# crowd_chase_el.net
KiCad netlist of a schematic drawn in EAGLE
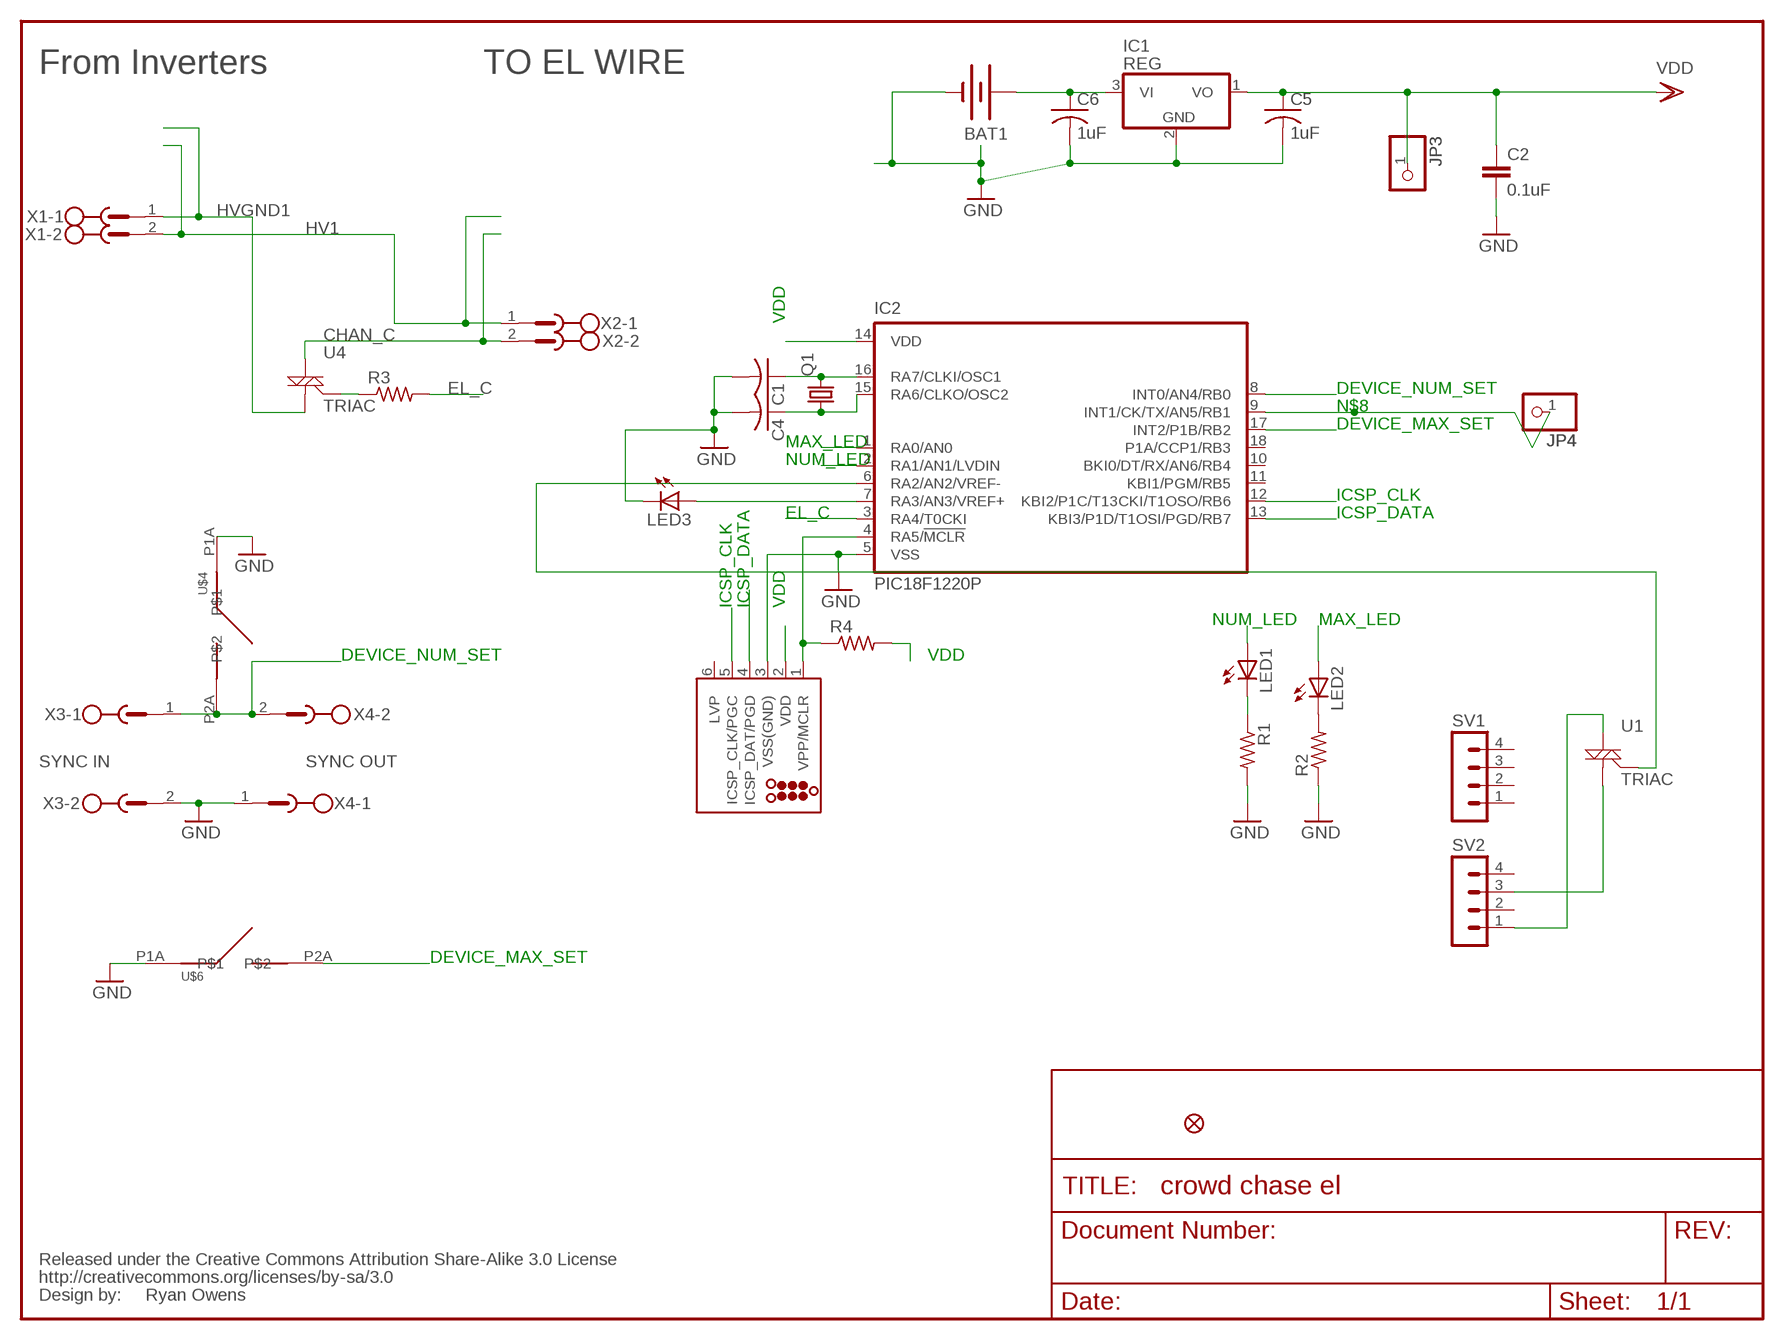
[diagram p0: schematic, sheet 1]

(export (version "E")
  (design (tool "Eeschema 10.0.6"))
  (components
    (comp (ref "BAT1")
      (value "BATTERY20SMD-L")
      (footprint "eagle-import:BATTCON_20MM")
      (libsource (lib "eagle-import") (part "BATTERY20SMD-L"))
    )
    (comp (ref "C1")
      (value "C-US025-025X050")
      (footprint "eagle-import:C025-025X050")
      (libsource (lib "eagle-import") (part "C-US025-025X050"))
    )
    (comp (ref "C2")
      (value "0.1uF")
      (footprint "eagle-import:CAP-PTH-SMALL2")
      (libsource (lib "eagle-import") (part "CAPPTH2"))
    )
    (comp (ref "C4")
      (value "C-US025-025X050")
      (footprint "eagle-import:C025-025X050")
      (libsource (lib "eagle-import") (part "C-US025-025X050"))
    )
    (comp (ref "C5")
      (value "1uF")
      (footprint "eagle-import:C025-025X050")
      (libsource (lib "eagle-import") (part "C-US025-025X050"))
    )
    (comp (ref "C6")
      (value "1uF")
      (footprint "eagle-import:C025-025X050")
      (libsource (lib "eagle-import") (part "C-US025-025X050"))
    )
    (comp (ref "IC1")
      (value "REG")
      (footprint "eagle-import:TO92")
      (libsource (lib "eagle-import") (part "78L05"))
    )
    (comp (ref "IC2")
      (value "PIC18F1220P")
      (footprint "eagle-import:DIL18")
      (fields (field (name "MF") "MICROCHIP") (field (name "MPN") "PIC18F1220-I/P"))
      (libsource (lib "eagle-import") (part "PIC18F120P2"))
    )
    (comp (ref "J2")
      (value "TC2030")
      (footprint "eagle-import:TC2030-MCP-NL-CP")
      (libsource (lib "eagle-import") (part "TC2030"))
    )
    (comp (ref "JP3")
      (value "PINHEADER_1X1")
      (footprint "eagle-import:HEADER_DIP_1X01")
      (libsource (lib "eagle-import") (part "PINHEADER_1X1"))
    )
    (comp (ref "JP4")
      (value "PINHEADER_1X1")
      (footprint "eagle-import:HEADER_DIP_1X01")
      (libsource (lib "eagle-import") (part "PINHEADER_1X1"))
    )
    (comp (ref "LED1")
      (value "LED3MM")
      (footprint "eagle-import:LED3MM")
      (libsource (lib "eagle-import") (part "LED3MM"))
    )
    (comp (ref "LED2")
      (value "LED3MM")
      (footprint "eagle-import:LED3MM")
      (libsource (lib "eagle-import") (part "LED3MM"))
    )
    (comp (ref "LED3")
      (value "LED3MM")
      (footprint "eagle-import:LED3MM")
      (libsource (lib "eagle-import") (part "LED3MM"))
    )
    (comp (ref "Q1")
      (value "CRYSTALHC49S")
      (footprint "eagle-import:HC49_S")
      (libsource (lib "eagle-import") (part "CRYSTALHC49S"))
    )
    (comp (ref "R1")
      (value "R-US_0204/5")
      (footprint "eagle-import:0204_5")
      (libsource (lib "eagle-import") (part "resistor_R-US_0204/5"))
    )
    (comp (ref "R2")
      (value "R-US_0204/5")
      (footprint "eagle-import:0204_5")
      (libsource (lib "eagle-import") (part "resistor_R-US_0204/5"))
    )
    (comp (ref "R3")
      (value "R-US_0204/5")
      (footprint "eagle-import:0204_5")
      (libsource (lib "eagle-import") (part "R-US_0204/5"))
    )
    (comp (ref "R4")
      (value "R-US_0204/5")
      (footprint "eagle-import:0204_5")
      (libsource (lib "eagle-import") (part "resistor_R-US_0204/5"))
    )
    (comp (ref "SV1")
      (value "MA04-1")
      (footprint "eagle-import:MA04-1")
      (libsource (lib "eagle-import") (part "MA04-1"))
    )
    (comp (ref "SV2")
      (value "MA04-1")
      (footprint "eagle-import:MA04-1")
      (libsource (lib "eagle-import") (part "MA04-1"))
    )
    (comp (ref "U$2")
      (value "FIDUCIAL1X2")
      (footprint "eagle-import:FIDUCIAL-1X2")
      (libsource (lib "eagle-import") (part "FIDUCIAL1X2"))
    )
    (comp (ref "U$4")
      (value "12MMTACT_MJTP1212")
      (footprint "eagle-import:MJTP1212")
      (libsource (lib "eagle-import") (part "12MMTACT_MJTP1212"))
    )
    (comp (ref "U$5")
      (value "CREATIVE_COMMONS")
      (footprint "eagle-import:CREATIVE_COMMONS")
      (libsource (lib "eagle-import") (part "CREATIVE_COMMONS"))
    )
    (comp (ref "U$6")
      (value "12MMTACT_MJTP1212")
      (footprint "eagle-import:MJTP1212")
      (libsource (lib "eagle-import") (part "12MMTACT_MJTP1212"))
    )
    (comp (ref "U1")
      (value "TRIAC")
      (footprint "eagle-import:TO-92")
      (libsource (lib "eagle-import") (part "TRIACPTH"))
    )
    (comp (ref "U4")
      (value "TRIAC")
      (footprint "eagle-import:TO-92")
      (libsource (lib "eagle-import") (part "TRIACPTH"))
    )
    (comp (ref "X1")
      (value "MSTBV2")
      (footprint "eagle-import:MSTBV2")
      (libsource (lib "eagle-import") (part "MSTBV2"))
    )
    (comp (ref "X2")
      (value "MSTBV2")
      (footprint "eagle-import:MSTBV2")
      (libsource (lib "eagle-import") (part "MSTBV2"))
    )
    (comp (ref "X3")
      (value "MSTBV2")
      (footprint "eagle-import:MSTBV2")
      (libsource (lib "eagle-import") (part "MSTBV2"))
    )
    (comp (ref "X4")
      (value "MSTBV2")
      (footprint "eagle-import:MSTBV2")
      (libsource (lib "eagle-import") (part "MSTBV2"))
    )
  )
  (nets
    (net (code "1") (name "/CHAN_C") (class "Default")
      (node (ref "U4") (pin "3") (pinfunction "M2_3") (pintype "bidirectional"))
      (node (ref "X2") (pin "2") (pinfunction "SK_2") (pintype "passive"))
    )
    (net (code "2") (name "/DEVICE_MAX_SET") (class "Default")
      (node (ref "IC2") (pin "17") (pinfunction "INT2/P1B/RB2_17") (pintype "bidirectional"))
      (node (ref "U$6") (pin "P2A") (pinfunction "P$2_P2A") (pintype "bidirectional"))
    )
    (net (code "3") (name "/DEVICE_NUM_SET") (class "Default")
      (node (ref "IC2") (pin "8") (pinfunction "INT0/AN4/RB0_8") (pintype "bidirectional"))
      (node (ref "U$4") (pin "P2A") (pinfunction "P$2_P2A") (pintype "bidirectional"))
      (node (ref "X3") (pin "1") (pinfunction "SK_1") (pintype "passive"))
      (node (ref "X4") (pin "2") (pinfunction "SK_2") (pintype "passive"))
    )
    (net (code "4") (name "/EL_C") (class "Default")
      (node (ref "IC2") (pin "3") (pinfunction "RA4/T0CKI_3") (pintype "bidirectional"))
      (node (ref "R3") (pin "2") (pinfunction "2_2") (pintype "passive"))
    )
    (net (code "5") (name "/HV1") (class "Default")
      (node (ref "X1") (pin "2") (pinfunction "SK_2") (pintype "passive"))
      (node (ref "X2") (pin "1") (pinfunction "SK_1") (pintype "passive"))
    )
    (net (code "6") (name "/HVGND1") (class "Default")
      (node (ref "U4") (pin "1") (pinfunction "M1_1") (pintype "bidirectional"))
      (node (ref "X1") (pin "1") (pinfunction "SK_1") (pintype "passive"))
    )
    (net (code "7") (name "/ICSP_CLK") (class "Default")
      (node (ref "IC2") (pin "12") (pinfunction "KBI2/P1C/T13CKI/T1OSO/RB6_12") (pintype "bidirectional"))
      (node (ref "J2") (pin "5") (pinfunction "ICSP_CLK/PGC_5") (pintype "output"))
    )
    (net (code "8") (name "/ICSP_DATA") (class "Default")
      (node (ref "IC2") (pin "13") (pinfunction "KBI3/P1D/T1OSI/PGD/RB7_13") (pintype "bidirectional"))
      (node (ref "J2") (pin "4") (pinfunction "ICSP_DAT/PGD_4") (pintype "bidirectional"))
    )
    (net (code "9") (name "/MAX_LED") (class "Default")
      (node (ref "IC2") (pin "1") (pinfunction "RA0/AN0_1") (pintype "bidirectional"))
      (node (ref "LED2") (pin "A") (pinfunction "A_A") (pintype "passive"))
    )
    (net (code "10") (name "/N$8") (class "Default")
      (node (ref "IC2") (pin "9") (pinfunction "INT1/CK/TX/AN5/RB1_9") (pintype "bidirectional"))
      (node (ref "JP4") (pin "1") (pinfunction "1_1") (pintype "passive"))
    )
    (net (code "11") (name "/NUM_LED") (class "Default")
      (node (ref "IC2") (pin "2") (pinfunction "RA1/AN1/LVDIN_2") (pintype "bidirectional"))
      (node (ref "LED1") (pin "A") (pinfunction "A_A") (pintype "passive"))
    )
    (net (code "12") (name "GND") (class "Default")
      (node (ref "BAT1") (pin "2") (pinfunction "-_2") (pintype "power_in"))
      (node (ref "C1") (pin "2") (pinfunction "2_2") (pintype "passive"))
      (node (ref "C2") (pin "2") (pinfunction "2_2") (pintype "passive"))
      (node (ref "C4") (pin "2") (pinfunction "2_2") (pintype "passive"))
      (node (ref "C5") (pin "2") (pinfunction "2_2") (pintype "passive"))
      (node (ref "C6") (pin "2") (pinfunction "2_2") (pintype "passive"))
      (node (ref "IC1") (pin "2") (pinfunction "GND_2") (pintype "passive"))
      (node (ref "IC2") (pin "5") (pinfunction "VSS_5") (pintype "power_in"))
      (node (ref "J2") (pin "3") (pinfunction "VSS(GND)_3") (pintype "power_in"))
      (node (ref "LED3") (pin "K") (pinfunction "C_K") (pintype "passive"))
      (node (ref "R1") (pin "2") (pinfunction "2_2") (pintype "passive"))
      (node (ref "R2") (pin "1") (pinfunction "1_1") (pintype "passive"))
      (node (ref "U$4") (pin "P1A") (pinfunction "P$1_P1A") (pintype "bidirectional"))
      (node (ref "U$6") (pin "P1A") (pinfunction "P$1_P1A") (pintype "bidirectional"))
      (node (ref "X3") (pin "2") (pinfunction "SK_2") (pintype "passive"))
      (node (ref "X4") (pin "1") (pinfunction "SK_1") (pintype "passive"))
    )
    (net (code "13") (name "Net-(BAT1-+)") (class "Default")
      (node (ref "BAT1") (pin "3") (pinfunction "+_3") (pintype "power_in"))
      (node (ref "C6") (pin "1") (pinfunction "1_1") (pintype "passive"))
      (node (ref "IC1") (pin "3") (pinfunction "VI_3") (pintype "input"))
    )
    (net (code "14") (name "Net-(IC2-RA2{slash}AN2{slash}VREF-)") (class "Default")
      (node (ref "IC2") (pin "6") (pinfunction "RA2/AN2/VREF-_6") (pintype "bidirectional"))
      (node (ref "U1") (pin "2") (pinfunction "G_2") (pintype "bidirectional"))
    )
    (net (code "15") (name "Net-(IC2-RA3{slash}AN3{slash}VREF+)") (class "Default")
      (node (ref "IC2") (pin "7") (pinfunction "RA3/AN3/VREF+_7") (pintype "bidirectional"))
      (node (ref "LED3") (pin "A") (pinfunction "A_A") (pintype "passive"))
    )
    (net (code "16") (name "Net-(IC2-RA5{slash}~{MCLR})") (class "Default")
      (node (ref "IC2") (pin "4") (pinfunction "RA5/~{MCLR}_4") (pintype "input"))
      (node (ref "J2") (pin "1") (pinfunction "VPP/MCLR_1") (pintype "passive"))
      (node (ref "R4") (pin "1") (pinfunction "1_1") (pintype "passive"))
    )
    (net (code "17") (name "Net-(IC2-RA6{slash}CLKO{slash}OSC2)") (class "Default")
      (node (ref "C4") (pin "1") (pinfunction "1_1") (pintype "passive"))
      (node (ref "IC2") (pin "15") (pinfunction "RA6/CLKO/OSC2_15") (pintype "bidirectional"))
      (node (ref "Q1") (pin "1") (pinfunction "1_1") (pintype "passive"))
    )
    (net (code "18") (name "Net-(IC2-RA7{slash}CLKI{slash}OSC1)") (class "Default")
      (node (ref "C1") (pin "1") (pinfunction "1_1") (pintype "passive"))
      (node (ref "IC2") (pin "16") (pinfunction "RA7/CLKI/OSC1_16") (pintype "bidirectional"))
      (node (ref "Q1") (pin "2") (pinfunction "2_2") (pintype "passive"))
    )
    (net (code "19") (name "Net-(LED1-C)") (class "Default")
      (node (ref "LED1") (pin "K") (pinfunction "C_K") (pintype "passive"))
      (node (ref "R1") (pin "1") (pinfunction "1_1") (pintype "passive"))
    )
    (net (code "20") (name "Net-(LED2-C)") (class "Default")
      (node (ref "LED2") (pin "K") (pinfunction "C_K") (pintype "passive"))
      (node (ref "R2") (pin "2") (pinfunction "2_2") (pintype "passive"))
    )
    (net (code "21") (name "Net-(U1-M1)") (class "Default")
      (node (ref "SV2") (pin "3") (pinfunction "3_3") (pintype "passive"))
      (node (ref "U1") (pin "1") (pinfunction "M1_1") (pintype "bidirectional"))
    )
    (net (code "22") (name "Net-(U1-M2)") (class "Default")
      (node (ref "SV2") (pin "1") (pinfunction "1_1") (pintype "passive"))
      (node (ref "U1") (pin "3") (pinfunction "M2_3") (pintype "bidirectional"))
    )
    (net (code "23") (name "Net-(U4-G)") (class "Default")
      (node (ref "R3") (pin "1") (pinfunction "1_1") (pintype "passive"))
      (node (ref "U4") (pin "2") (pinfunction "G_2") (pintype "bidirectional"))
    )
    (net (code "24") (name "VDD") (class "Default")
      (node (ref "C2") (pin "1") (pinfunction "1_1") (pintype "passive"))
      (node (ref "C5") (pin "1") (pinfunction "1_1") (pintype "passive"))
      (node (ref "IC1") (pin "1") (pinfunction "VO_1") (pintype "passive"))
      (node (ref "IC2") (pin "14") (pinfunction "VDD_14") (pintype "power_in"))
      (node (ref "J2") (pin "2") (pinfunction "VDD_2") (pintype "power_in"))
      (node (ref "JP3") (pin "1") (pinfunction "1_1") (pintype "passive"))
      (node (ref "R4") (pin "2") (pinfunction "2_2") (pintype "passive"))
    )
    (net (code "25") (name "unconnected-(IC2-BKI0{slash}DT{slash}RX{slash}AN6{slash}RB4-Pad10)") (class "Default")
      (node (ref "IC2") (pin "10") (pinfunction "BKI0/DT/RX/AN6/RB4_10") (pintype "bidirectional"))
    )
    (net (code "26") (name "unconnected-(IC2-KBI1{slash}PGM{slash}RB5-Pad11)") (class "Default")
      (node (ref "IC2") (pin "11") (pinfunction "KBI1/PGM/RB5_11") (pintype "bidirectional"))
    )
    (net (code "27") (name "unconnected-(IC2-P1A{slash}CCP1{slash}RB3-Pad18)") (class "Default")
      (node (ref "IC2") (pin "18") (pinfunction "P1A/CCP1/RB3_18") (pintype "bidirectional"))
    )
    (net (code "28") (name "unconnected-(J2-LVP-Pad6)") (class "Default")
      (node (ref "J2") (pin "6") (pinfunction "LVP_6") (pintype "bidirectional"))
    )
    (net (code "29") (name "unconnected-(SV1-Pad1)") (class "Default")
      (node (ref "SV1") (pin "1") (pinfunction "1_1") (pintype "passive"))
    )
    (net (code "30") (name "unconnected-(SV1-Pad2)") (class "Default")
      (node (ref "SV1") (pin "2") (pinfunction "2_2") (pintype "passive"))
    )
    (net (code "31") (name "unconnected-(SV1-Pad3)") (class "Default")
      (node (ref "SV1") (pin "3") (pinfunction "3_3") (pintype "passive"))
    )
    (net (code "32") (name "unconnected-(SV1-Pad4)") (class "Default")
      (node (ref "SV1") (pin "4") (pinfunction "4_4") (pintype "passive"))
    )
    (net (code "33") (name "unconnected-(SV2-Pad2)") (class "Default")
      (node (ref "SV2") (pin "2") (pinfunction "2_2") (pintype "passive"))
    )
    (net (code "34") (name "unconnected-(SV2-Pad4)") (class "Default")
      (node (ref "SV2") (pin "4") (pinfunction "4_4") (pintype "passive"))
    )
  )
)
